# board.net
KiCad netlist of a schematic drawn in EAGLE
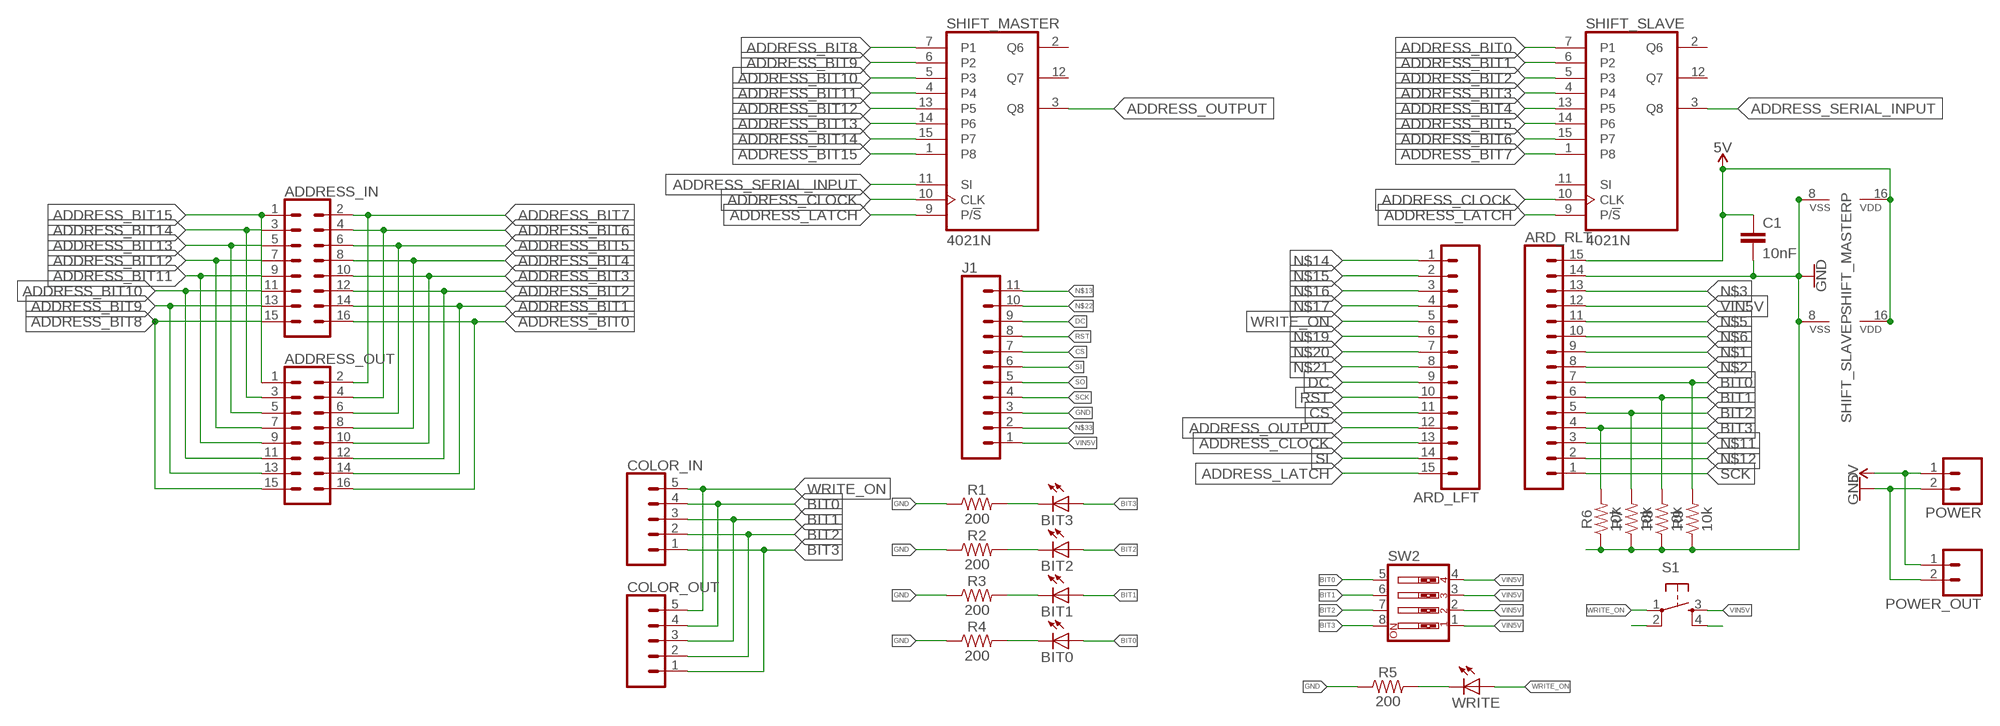
[diagram p0: schematic, sheet 1]

(export (version "E")
  (design (tool "Eeschema 10.0.6"))
  (components
    (comp (ref "ADDRESS_IN")
      (value "CONN_08X2")
      (footprint "eagle-import:2X8")
      (libsource (lib "eagle-import") (part "CONN_08X2"))
    )
    (comp (ref "ADDRESS_OUT")
      (value "CONN_08X2")
      (footprint "eagle-import:2X8")
      (libsource (lib "eagle-import") (part "CONN_08X2"))
    )
    (comp (ref "ARD_LFT")
      (value "CONN_15")
      (footprint "eagle-import:1X15")
      (libsource (lib "eagle-import") (part "CONN_15"))
    )
    (comp (ref "ARD_RLT")
      (value "CONN_15")
      (footprint "eagle-import:1X15")
      (libsource (lib "eagle-import") (part "CONN_15"))
    )
    (comp (ref "BIT0")
      (value "LED5MM")
      (footprint "eagle-import:LED5MM")
      (libsource (lib "eagle-import") (part "LED5MM"))
    )
    (comp (ref "BIT1")
      (value "LED5MM")
      (footprint "eagle-import:LED5MM")
      (libsource (lib "eagle-import") (part "LED5MM"))
    )
    (comp (ref "BIT2")
      (value "LED5MM")
      (footprint "eagle-import:LED5MM")
      (libsource (lib "eagle-import") (part "LED5MM"))
    )
    (comp (ref "BIT3")
      (value "LED5MM")
      (footprint "eagle-import:LED5MM")
      (libsource (lib "eagle-import") (part "LED5MM"))
    )
    (comp (ref "C1")
      (value "10nF")
      (footprint "eagle-import:CAP-PTH-10MM")
      (libsource (lib "eagle-import") (part "10NF-PTH-10MM-10000V-1-%"))
    )
    (comp (ref "COLOR_IN")
      (value "CONN_05")
      (footprint "eagle-import:1X05")
      (libsource (lib "eagle-import") (part "CONN_05"))
    )
    (comp (ref "COLOR_OUT")
      (value "CONN_05")
      (footprint "eagle-import:1X05")
      (libsource (lib "eagle-import") (part "CONN_05"))
    )
    (comp (ref "J1")
      (value "CONN_11")
      (footprint "eagle-import:1X11")
      (libsource (lib "eagle-import") (part "CONN_11"))
    )
    (comp (ref "POWER")
      (value "CONN_02")
      (footprint "eagle-import:1X02")
      (libsource (lib "eagle-import") (part "CONN_02"))
    )
    (comp (ref "POWER_OUT")
      (value "CONN_02")
      (footprint "eagle-import:1X02")
      (libsource (lib "eagle-import") (part "CONN_02"))
    )
    (comp (ref "R1")
      (value "200")
      (footprint "eagle-import:AXIAL-0.3")
      (libsource (lib "eagle-import") (part "RESISTORAXIAL-0.3"))
    )
    (comp (ref "R2")
      (value "200")
      (footprint "eagle-import:AXIAL-0.3")
      (libsource (lib "eagle-import") (part "RESISTORAXIAL-0.3"))
    )
    (comp (ref "R3")
      (value "200")
      (footprint "eagle-import:AXIAL-0.3")
      (libsource (lib "eagle-import") (part "RESISTORAXIAL-0.3"))
    )
    (comp (ref "R4")
      (value "200")
      (footprint "eagle-import:AXIAL-0.3")
      (libsource (lib "eagle-import") (part "RESISTORAXIAL-0.3"))
    )
    (comp (ref "R5")
      (value "200")
      (footprint "eagle-import:AXIAL-0.3")
      (libsource (lib "eagle-import") (part "RESISTORAXIAL-0.3"))
    )
    (comp (ref "R6")
      (value "10k")
      (footprint "eagle-import:AXIAL-0.3")
      (libsource (lib "eagle-import") (part "10KOHM-HORIZ-1/4W-5%"))
    )
    (comp (ref "R7")
      (value "10k")
      (footprint "eagle-import:AXIAL-0.3")
      (libsource (lib "eagle-import") (part "10KOHM-HORIZ-1/4W-5%"))
    )
    (comp (ref "R8")
      (value "10k")
      (footprint "eagle-import:AXIAL-0.3")
      (libsource (lib "eagle-import") (part "10KOHM-HORIZ-1/4W-5%"))
    )
    (comp (ref "R9")
      (value "10k")
      (footprint "eagle-import:AXIAL-0.3")
      (libsource (lib "eagle-import") (part "10KOHM-HORIZ-1/4W-5%"))
    )
    (comp (ref "S1")
      (value "TAC_SWITCHPTH")
      (footprint "eagle-import:TACTILE-PTH")
      (libsource (lib "eagle-import") (part "TAC_SWITCHPTH"))
    )
    (comp (ref "SHIFT_MASTER")
      (value "4021N")
      (footprint "eagle-import:DIL16")
      (libsource (lib "eagle-import") (part "4021N"))
    )
    (comp (ref "SHIFT_SLAVE")
      (value "4021N")
      (footprint "eagle-import:DIL16")
      (libsource (lib "eagle-import") (part "4021N"))
    )
    (comp (ref "SW2")
      (value "SW_DIP-4")
      (footprint "eagle-import:EDG-04")
      (libsource (lib "eagle-import") (part "SW_DIP-4"))
    )
    (comp (ref "WRITE")
      (value "LED5MM")
      (footprint "eagle-import:LED5MM")
      (libsource (lib "eagle-import") (part "LED5MM"))
    )
  )
  (nets
    (net (code "1") (name "5V") (class "Default")
      (node (ref "ARD_RLT") (pin "15") (pinfunction "15_15") (pintype "passive"))
      (node (ref "C1") (pin "1") (pinfunction "1_1") (pintype "passive"))
      (node (ref "POWER") (pin "1") (pinfunction "1_1") (pintype "passive"))
      (node (ref "POWER_OUT") (pin "1") (pinfunction "1_1") (pintype "passive"))
      (node (ref "SHIFT_MASTER") (pin "16") (pinfunction "VDD_16") (pintype "power_in"))
      (node (ref "SHIFT_SLAVE") (pin "16") (pinfunction "VDD_16") (pintype "power_in"))
    )
    (net (code "2") (name "ADDRESS_BIT0") (class "Default")
      (node (ref "ADDRESS_IN") (pin "16") (pinfunction "16_16") (pintype "passive"))
      (node (ref "ADDRESS_OUT") (pin "16") (pinfunction "16_16") (pintype "passive"))
      (node (ref "SHIFT_SLAVE") (pin "7") (pinfunction "P1_7") (pintype "input"))
    )
    (net (code "3") (name "ADDRESS_BIT1") (class "Default")
      (node (ref "ADDRESS_IN") (pin "14") (pinfunction "14_14") (pintype "passive"))
      (node (ref "ADDRESS_OUT") (pin "14") (pinfunction "14_14") (pintype "passive"))
      (node (ref "SHIFT_SLAVE") (pin "6") (pinfunction "P2_6") (pintype "input"))
    )
    (net (code "4") (name "ADDRESS_BIT2") (class "Default")
      (node (ref "ADDRESS_IN") (pin "12") (pinfunction "12_12") (pintype "passive"))
      (node (ref "ADDRESS_OUT") (pin "12") (pinfunction "12_12") (pintype "passive"))
      (node (ref "SHIFT_SLAVE") (pin "5") (pinfunction "P3_5") (pintype "input"))
    )
    (net (code "5") (name "ADDRESS_BIT3") (class "Default")
      (node (ref "ADDRESS_IN") (pin "10") (pinfunction "10_10") (pintype "passive"))
      (node (ref "ADDRESS_OUT") (pin "10") (pinfunction "10_10") (pintype "passive"))
      (node (ref "SHIFT_SLAVE") (pin "4") (pinfunction "P4_4") (pintype "input"))
    )
    (net (code "6") (name "ADDRESS_BIT4") (class "Default")
      (node (ref "ADDRESS_IN") (pin "8") (pinfunction "8_8") (pintype "passive"))
      (node (ref "ADDRESS_OUT") (pin "8") (pinfunction "8_8") (pintype "passive"))
      (node (ref "SHIFT_SLAVE") (pin "13") (pinfunction "P5_13") (pintype "input"))
    )
    (net (code "7") (name "ADDRESS_BIT5") (class "Default")
      (node (ref "ADDRESS_IN") (pin "6") (pinfunction "6_6") (pintype "passive"))
      (node (ref "ADDRESS_OUT") (pin "6") (pinfunction "6_6") (pintype "passive"))
      (node (ref "SHIFT_SLAVE") (pin "14") (pinfunction "P6_14") (pintype "input"))
    )
    (net (code "8") (name "ADDRESS_BIT6") (class "Default")
      (node (ref "ADDRESS_IN") (pin "4") (pinfunction "4_4") (pintype "passive"))
      (node (ref "ADDRESS_OUT") (pin "4") (pinfunction "4_4") (pintype "passive"))
      (node (ref "SHIFT_SLAVE") (pin "15") (pinfunction "P7_15") (pintype "input"))
    )
    (net (code "9") (name "ADDRESS_BIT7") (class "Default")
      (node (ref "ADDRESS_IN") (pin "2") (pinfunction "2_2") (pintype "passive"))
      (node (ref "ADDRESS_OUT") (pin "2") (pinfunction "2_2") (pintype "passive"))
      (node (ref "SHIFT_SLAVE") (pin "1") (pinfunction "P8_1") (pintype "input"))
    )
    (net (code "10") (name "ADDRESS_BIT8") (class "Default")
      (node (ref "ADDRESS_IN") (pin "15") (pinfunction "15_15") (pintype "passive"))
      (node (ref "ADDRESS_OUT") (pin "15") (pinfunction "15_15") (pintype "passive"))
      (node (ref "SHIFT_MASTER") (pin "7") (pinfunction "P1_7") (pintype "input"))
    )
    (net (code "11") (name "ADDRESS_BIT9") (class "Default")
      (node (ref "ADDRESS_IN") (pin "13") (pinfunction "13_13") (pintype "passive"))
      (node (ref "ADDRESS_OUT") (pin "13") (pinfunction "13_13") (pintype "passive"))
      (node (ref "SHIFT_MASTER") (pin "6") (pinfunction "P2_6") (pintype "input"))
    )
    (net (code "12") (name "ADDRESS_BIT10") (class "Default")
      (node (ref "ADDRESS_IN") (pin "11") (pinfunction "11_11") (pintype "passive"))
      (node (ref "ADDRESS_OUT") (pin "11") (pinfunction "11_11") (pintype "passive"))
      (node (ref "SHIFT_MASTER") (pin "5") (pinfunction "P3_5") (pintype "input"))
    )
    (net (code "13") (name "ADDRESS_BIT11") (class "Default")
      (node (ref "ADDRESS_IN") (pin "9") (pinfunction "9_9") (pintype "passive"))
      (node (ref "ADDRESS_OUT") (pin "9") (pinfunction "9_9") (pintype "passive"))
      (node (ref "SHIFT_MASTER") (pin "4") (pinfunction "P4_4") (pintype "input"))
    )
    (net (code "14") (name "ADDRESS_BIT12") (class "Default")
      (node (ref "ADDRESS_IN") (pin "7") (pinfunction "7_7") (pintype "passive"))
      (node (ref "ADDRESS_OUT") (pin "7") (pinfunction "7_7") (pintype "passive"))
      (node (ref "SHIFT_MASTER") (pin "13") (pinfunction "P5_13") (pintype "input"))
    )
    (net (code "15") (name "ADDRESS_BIT13") (class "Default")
      (node (ref "ADDRESS_IN") (pin "5") (pinfunction "5_5") (pintype "passive"))
      (node (ref "ADDRESS_OUT") (pin "5") (pinfunction "5_5") (pintype "passive"))
      (node (ref "SHIFT_MASTER") (pin "14") (pinfunction "P6_14") (pintype "input"))
    )
    (net (code "16") (name "ADDRESS_BIT14") (class "Default")
      (node (ref "ADDRESS_IN") (pin "3") (pinfunction "3_3") (pintype "passive"))
      (node (ref "ADDRESS_OUT") (pin "3") (pinfunction "3_3") (pintype "passive"))
      (node (ref "SHIFT_MASTER") (pin "15") (pinfunction "P7_15") (pintype "input"))
    )
    (net (code "17") (name "ADDRESS_BIT15") (class "Default")
      (node (ref "ADDRESS_IN") (pin "1") (pinfunction "1_1") (pintype "passive"))
      (node (ref "ADDRESS_OUT") (pin "1") (pinfunction "1_1") (pintype "passive"))
      (node (ref "SHIFT_MASTER") (pin "1") (pinfunction "P8_1") (pintype "input"))
    )
    (net (code "18") (name "ADDRESS_CLOCK") (class "Default")
      (node (ref "ARD_LFT") (pin "13") (pinfunction "13_13") (pintype "passive"))
      (node (ref "SHIFT_MASTER") (pin "10") (pinfunction "CLK_10") (pintype "input"))
      (node (ref "SHIFT_SLAVE") (pin "10") (pinfunction "CLK_10") (pintype "input"))
    )
    (net (code "19") (name "ADDRESS_LATCH") (class "Default")
      (node (ref "ARD_LFT") (pin "15") (pinfunction "15_15") (pintype "passive"))
      (node (ref "SHIFT_MASTER") (pin "9") (pinfunction "P/~{S}_9") (pintype "input"))
      (node (ref "SHIFT_SLAVE") (pin "9") (pinfunction "P/~{S}_9") (pintype "input"))
    )
    (net (code "20") (name "ADDRESS_OUTPUT") (class "Default")
      (node (ref "ARD_LFT") (pin "12") (pinfunction "12_12") (pintype "passive"))
      (node (ref "SHIFT_MASTER") (pin "3") (pinfunction "Q8_3") (pintype "output"))
    )
    (net (code "21") (name "ADDRESS_SERIAL_INPUT") (class "Default")
      (node (ref "SHIFT_MASTER") (pin "11") (pinfunction "SI_11") (pintype "input"))
      (node (ref "SHIFT_SLAVE") (pin "3") (pinfunction "Q8_3") (pintype "output"))
    )
    (net (code "22") (name "BIT0") (class "Default")
      (node (ref "ARD_RLT") (pin "7") (pinfunction "7_7") (pintype "passive"))
      (node (ref "BIT0") (pin "A") (pinfunction "A_A") (pintype "passive"))
      (node (ref "COLOR_IN") (pin "4") (pinfunction "4_4") (pintype "passive"))
      (node (ref "COLOR_OUT") (pin "4") (pinfunction "4_4") (pintype "passive"))
      (node (ref "R9") (pin "P$2") (pinfunction "2_P$2") (pintype "passive"))
      (node (ref "SW2") (pin "5") (pinfunction "5_5") (pintype "passive"))
    )
    (net (code "23") (name "BIT1") (class "Default")
      (node (ref "ARD_RLT") (pin "6") (pinfunction "6_6") (pintype "passive"))
      (node (ref "BIT1") (pin "A") (pinfunction "A_A") (pintype "passive"))
      (node (ref "COLOR_IN") (pin "3") (pinfunction "3_3") (pintype "passive"))
      (node (ref "COLOR_OUT") (pin "3") (pinfunction "3_3") (pintype "passive"))
      (node (ref "R8") (pin "P$2") (pinfunction "2_P$2") (pintype "passive"))
      (node (ref "SW2") (pin "6") (pinfunction "6_6") (pintype "passive"))
    )
    (net (code "24") (name "BIT2") (class "Default")
      (node (ref "ARD_RLT") (pin "5") (pinfunction "5_5") (pintype "passive"))
      (node (ref "BIT2") (pin "A") (pinfunction "A_A") (pintype "passive"))
      (node (ref "COLOR_IN") (pin "2") (pinfunction "2_2") (pintype "passive"))
      (node (ref "COLOR_OUT") (pin "2") (pinfunction "2_2") (pintype "passive"))
      (node (ref "R7") (pin "P$2") (pinfunction "2_P$2") (pintype "passive"))
      (node (ref "SW2") (pin "7") (pinfunction "7_7") (pintype "passive"))
    )
    (net (code "25") (name "BIT3") (class "Default")
      (node (ref "ARD_RLT") (pin "4") (pinfunction "4_4") (pintype "passive"))
      (node (ref "BIT3") (pin "A") (pinfunction "A_A") (pintype "passive"))
      (node (ref "COLOR_IN") (pin "1") (pinfunction "1_1") (pintype "passive"))
      (node (ref "COLOR_OUT") (pin "1") (pinfunction "1_1") (pintype "passive"))
      (node (ref "R6") (pin "P$2") (pinfunction "2_P$2") (pintype "passive"))
      (node (ref "SW2") (pin "8") (pinfunction "8_8") (pintype "passive"))
    )
    (net (code "26") (name "CS") (class "Default")
      (node (ref "ARD_LFT") (pin "11") (pinfunction "11_11") (pintype "passive"))
      (node (ref "J1") (pin "7") (pinfunction "7_7") (pintype "passive"))
    )
    (net (code "27") (name "DC") (class "Default")
      (node (ref "ARD_LFT") (pin "9") (pinfunction "9_9") (pintype "passive"))
      (node (ref "J1") (pin "9") (pinfunction "9_9") (pintype "passive"))
    )
    (net (code "28") (name "GND") (class "Default")
      (node (ref "ARD_RLT") (pin "14") (pinfunction "14_14") (pintype "passive"))
      (node (ref "C1") (pin "2") (pinfunction "2_2") (pintype "passive"))
      (node (ref "J1") (pin "3") (pinfunction "3_3") (pintype "passive"))
      (node (ref "POWER") (pin "2") (pinfunction "2_2") (pintype "passive"))
      (node (ref "POWER_OUT") (pin "2") (pinfunction "2_2") (pintype "passive"))
      (node (ref "R1") (pin "P$1") (pinfunction "1_P$1") (pintype "passive"))
      (node (ref "R2") (pin "P$1") (pinfunction "1_P$1") (pintype "passive"))
      (node (ref "R3") (pin "P$1") (pinfunction "1_P$1") (pintype "passive"))
      (node (ref "R4") (pin "P$1") (pinfunction "1_P$1") (pintype "passive"))
      (node (ref "R5") (pin "P$1") (pinfunction "1_P$1") (pintype "passive"))
      (node (ref "R6") (pin "P$1") (pinfunction "1_P$1") (pintype "passive"))
      (node (ref "R7") (pin "P$1") (pinfunction "1_P$1") (pintype "passive"))
      (node (ref "R8") (pin "P$1") (pinfunction "1_P$1") (pintype "passive"))
      (node (ref "R9") (pin "P$1") (pinfunction "1_P$1") (pintype "passive"))
      (node (ref "SHIFT_MASTER") (pin "8") (pinfunction "VSS_8") (pintype "power_in"))
      (node (ref "SHIFT_SLAVE") (pin "8") (pinfunction "VSS_8") (pintype "power_in"))
    )
    (net (code "29") (name "N$1") (class "Default")
      (node (ref "ARD_RLT") (pin "9") (pinfunction "9_9") (pintype "passive"))
    )
    (net (code "30") (name "N$2") (class "Default")
      (node (ref "ARD_RLT") (pin "8") (pinfunction "8_8") (pintype "passive"))
    )
    (net (code "31") (name "N$3") (class "Default")
      (node (ref "ARD_RLT") (pin "13") (pinfunction "13_13") (pintype "passive"))
    )
    (net (code "32") (name "N$5") (class "Default")
      (node (ref "ARD_RLT") (pin "11") (pinfunction "11_11") (pintype "passive"))
    )
    (net (code "33") (name "N$6") (class "Default")
      (node (ref "ARD_RLT") (pin "10") (pinfunction "10_10") (pintype "passive"))
    )
    (net (code "34") (name "N$11") (class "Default")
      (node (ref "ARD_RLT") (pin "3") (pinfunction "3_3") (pintype "passive"))
    )
    (net (code "35") (name "N$12") (class "Default")
      (node (ref "ARD_RLT") (pin "2") (pinfunction "2_2") (pintype "passive"))
    )
    (net (code "36") (name "N$13") (class "Default")
      (node (ref "J1") (pin "11") (pinfunction "11_11") (pintype "passive"))
    )
    (net (code "37") (name "N$14") (class "Default")
      (node (ref "ARD_LFT") (pin "1") (pinfunction "1_1") (pintype "passive"))
    )
    (net (code "38") (name "N$15") (class "Default")
      (node (ref "ARD_LFT") (pin "2") (pinfunction "2_2") (pintype "passive"))
    )
    (net (code "39") (name "N$16") (class "Default")
      (node (ref "ARD_LFT") (pin "3") (pinfunction "3_3") (pintype "passive"))
    )
    (net (code "40") (name "N$17") (class "Default")
      (node (ref "ARD_LFT") (pin "4") (pinfunction "4_4") (pintype "passive"))
    )
    (net (code "41") (name "N$19") (class "Default")
      (node (ref "ARD_LFT") (pin "6") (pinfunction "6_6") (pintype "passive"))
    )
    (net (code "42") (name "N$20") (class "Default")
      (node (ref "ARD_LFT") (pin "7") (pinfunction "7_7") (pintype "passive"))
    )
    (net (code "43") (name "N$21") (class "Default")
      (node (ref "ARD_LFT") (pin "8") (pinfunction "8_8") (pintype "passive"))
    )
    (net (code "44") (name "N$22") (class "Default")
      (node (ref "J1") (pin "10") (pinfunction "10_10") (pintype "passive"))
    )
    (net (code "45") (name "N$33") (class "Default")
      (node (ref "J1") (pin "2") (pinfunction "2_2") (pintype "passive"))
    )
    (net (code "46") (name "Net-(BIT0-C)") (class "Default")
      (node (ref "BIT0") (pin "K") (pinfunction "C_K") (pintype "passive"))
      (node (ref "R4") (pin "P$2") (pinfunction "2_P$2") (pintype "passive"))
    )
    (net (code "47") (name "Net-(BIT1-C)") (class "Default")
      (node (ref "BIT1") (pin "K") (pinfunction "C_K") (pintype "passive"))
      (node (ref "R3") (pin "P$2") (pinfunction "2_P$2") (pintype "passive"))
    )
    (net (code "48") (name "Net-(BIT2-C)") (class "Default")
      (node (ref "BIT2") (pin "K") (pinfunction "C_K") (pintype "passive"))
      (node (ref "R2") (pin "P$2") (pinfunction "2_P$2") (pintype "passive"))
    )
    (net (code "49") (name "Net-(BIT3-C)") (class "Default")
      (node (ref "BIT3") (pin "K") (pinfunction "C_K") (pintype "passive"))
      (node (ref "R1") (pin "P$2") (pinfunction "2_P$2") (pintype "passive"))
    )
    (net (code "50") (name "Net-(R5-2)") (class "Default")
      (node (ref "R5") (pin "P$2") (pinfunction "2_P$2") (pintype "passive"))
      (node (ref "WRITE") (pin "K") (pinfunction "C_K") (pintype "passive"))
    )
    (net (code "51") (name "RST") (class "Default")
      (node (ref "ARD_LFT") (pin "10") (pinfunction "10_10") (pintype "passive"))
      (node (ref "J1") (pin "8") (pinfunction "8_8") (pintype "passive"))
    )
    (net (code "52") (name "SCK") (class "Default")
      (node (ref "ARD_RLT") (pin "1") (pinfunction "1_1") (pintype "passive"))
      (node (ref "J1") (pin "4") (pinfunction "4_4") (pintype "passive"))
    )
    (net (code "53") (name "SI") (class "Default")
      (node (ref "ARD_LFT") (pin "14") (pinfunction "14_14") (pintype "passive"))
      (node (ref "J1") (pin "6") (pinfunction "6_6") (pintype "passive"))
    )
    (net (code "54") (name "SO") (class "Default")
      (node (ref "J1") (pin "5") (pinfunction "5_5") (pintype "passive"))
    )
    (net (code "55") (name "VIN5V") (class "Default")
      (node (ref "ARD_RLT") (pin "12") (pinfunction "12_12") (pintype "passive"))
      (node (ref "J1") (pin "1") (pinfunction "1_1") (pintype "passive"))
      (node (ref "S1") (pin "3") (pinfunction "3_3") (pintype "passive"))
      (node (ref "SW2") (pin "1") (pinfunction "1_1") (pintype "passive"))
      (node (ref "SW2") (pin "2") (pinfunction "2_2") (pintype "passive"))
      (node (ref "SW2") (pin "3") (pinfunction "3_3") (pintype "passive"))
      (node (ref "SW2") (pin "4") (pinfunction "4_4") (pintype "passive"))
    )
    (net (code "56") (name "WRITE_ON") (class "Default")
      (node (ref "ARD_LFT") (pin "5") (pinfunction "5_5") (pintype "passive"))
      (node (ref "COLOR_IN") (pin "5") (pinfunction "5_5") (pintype "passive"))
      (node (ref "COLOR_OUT") (pin "5") (pinfunction "5_5") (pintype "passive"))
      (node (ref "S1") (pin "1") (pinfunction "1_1") (pintype "passive"))
      (node (ref "WRITE") (pin "A") (pinfunction "A_A") (pintype "passive"))
    )
    (net (code "57") (name "unconnected-(S1-Pad2)") (class "Default")
      (node (ref "S1") (pin "2") (pinfunction "2_2") (pintype "passive"))
    )
    (net (code "58") (name "unconnected-(S1-Pad4)") (class "Default")
      (node (ref "S1") (pin "4") (pinfunction "4_4") (pintype "passive"))
    )
    (net (code "59") (name "unconnected-(SHIFT_MASTERA-Q6-Pad2)") (class "Default")
      (node (ref "SHIFT_MASTER") (pin "2") (pinfunction "Q6_2") (pintype "output"))
    )
    (net (code "60") (name "unconnected-(SHIFT_MASTERA-Q7-Pad12)") (class "Default")
      (node (ref "SHIFT_MASTER") (pin "12") (pinfunction "Q7_12") (pintype "output"))
    )
    (net (code "61") (name "unconnected-(SHIFT_SLAVEA-Q6-Pad2)") (class "Default")
      (node (ref "SHIFT_SLAVE") (pin "2") (pinfunction "Q6_2") (pintype "output"))
    )
    (net (code "62") (name "unconnected-(SHIFT_SLAVEA-Q7-Pad12)") (class "Default")
      (node (ref "SHIFT_SLAVE") (pin "12") (pinfunction "Q7_12") (pintype "output"))
    )
    (net (code "63") (name "unconnected-(SHIFT_SLAVEA-SI-Pad11)") (class "Default")
      (node (ref "SHIFT_SLAVE") (pin "11") (pinfunction "SI_11") (pintype "input"))
    )
  )
)
